# shoe_board.net
KiCad netlist of a schematic drawn in EAGLE
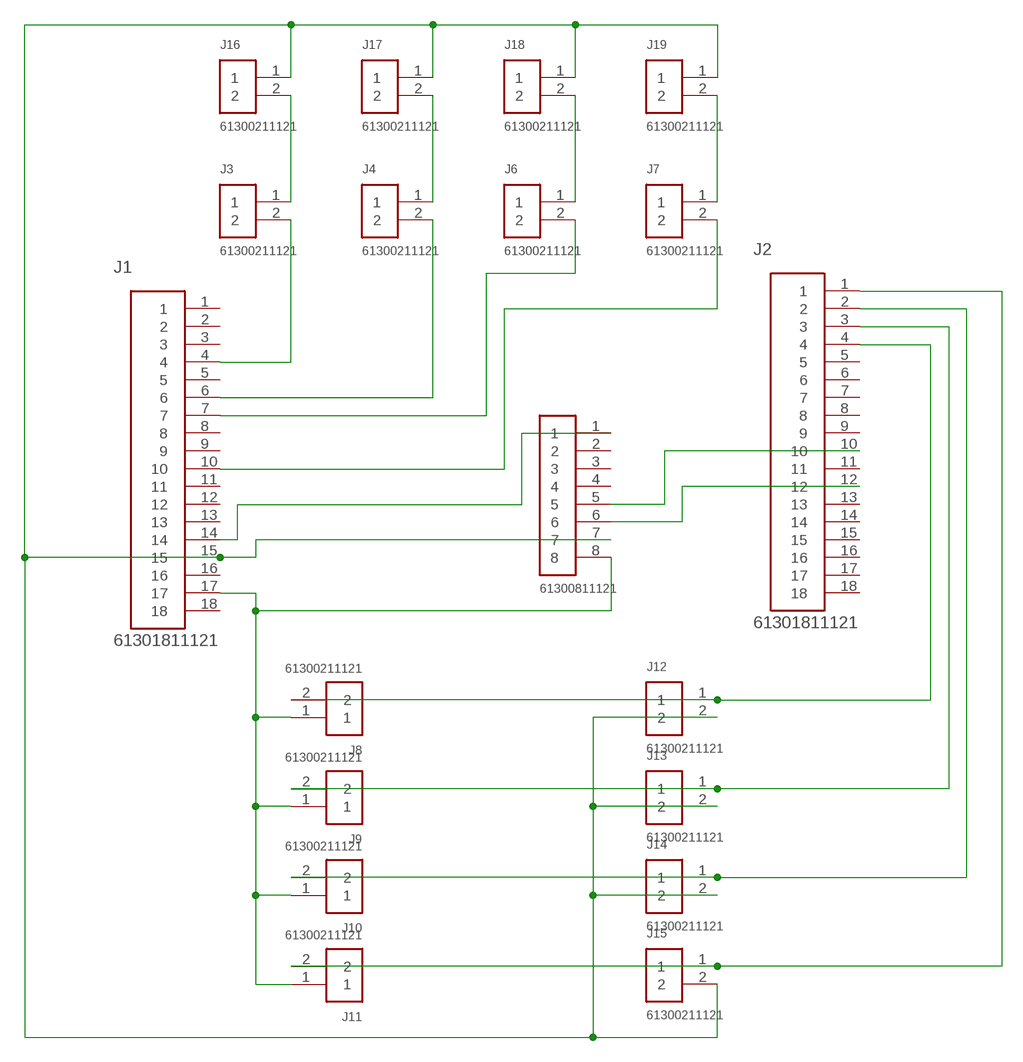
[diagram p0: schematic, sheet 1]

(export (version "E")
  (design (tool "Eeschema 10.0.6"))
  (components
    (comp (ref "J1")
      (value "61301811121")
      (footprint "eagle-import:61301811121")
      (fields
        (field (name "DIGIKEY_PART_NUMBER") "732-5328-ND")
        (field (name "MANUFACTURER") "Wurth Electronics Inc.")
        (field (name "CREATED_BY") "PCBLayout.com")
      )
      (libsource (lib "eagle-import") (part "61301811121"))
    )
    (comp (ref "J2")
      (value "61301811121")
      (footprint "eagle-import:61301811121")
      (fields
        (field (name "DIGIKEY_PART_NUMBER") "732-5328-ND")
        (field (name "MANUFACTURER") "Wurth Electronics Inc.")
        (field (name "CREATED_BY") "PCBLayout.com")
      )
      (libsource (lib "eagle-import") (part "61301811121"))
    )
    (comp (ref "J3")
      (value "61300211121")
      (footprint "eagle-import:61300211121")
      (fields
        (field (name "DIGI_KEY_PART_NUMBER") "732-5315-ND")
        (field (name "MANUFACTURER") "Wurth Electronics Inc.")
        (field (name "CREATED_BY") "PCBLayout.com")
      )
      (libsource (lib "eagle-import") (part "61300211121"))
    )
    (comp (ref "J4")
      (value "61300211121")
      (footprint "eagle-import:61300211121")
      (fields
        (field (name "DIGI_KEY_PART_NUMBER") "732-5315-ND")
        (field (name "MANUFACTURER") "Wurth Electronics Inc.")
        (field (name "CREATED_BY") "PCBLayout.com")
      )
      (libsource (lib "eagle-import") (part "61300211121"))
    )
    (comp (ref "J6")
      (value "61300211121")
      (footprint "eagle-import:61300211121")
      (fields
        (field (name "DIGI_KEY_PART_NUMBER") "732-5315-ND")
        (field (name "MANUFACTURER") "Wurth Electronics Inc.")
        (field (name "CREATED_BY") "PCBLayout.com")
      )
      (libsource (lib "eagle-import") (part "61300211121"))
    )
    (comp (ref "J7")
      (value "61300211121")
      (footprint "eagle-import:61300211121")
      (fields
        (field (name "DIGI_KEY_PART_NUMBER") "732-5315-ND")
        (field (name "MANUFACTURER") "Wurth Electronics Inc.")
        (field (name "CREATED_BY") "PCBLayout.com")
      )
      (libsource (lib "eagle-import") (part "61300211121"))
    )
    (comp (ref "J8")
      (value "61300211121")
      (footprint "eagle-import:61300211121")
      (fields
        (field (name "DIGI_KEY_PART_NUMBER") "732-5315-ND")
        (field (name "MANUFACTURER") "Wurth Electronics Inc.")
        (field (name "CREATED_BY") "PCBLayout.com")
      )
      (libsource (lib "eagle-import") (part "61300211121"))
    )
    (comp (ref "J9")
      (value "61300211121")
      (footprint "eagle-import:61300211121")
      (fields
        (field (name "DIGI_KEY_PART_NUMBER") "732-5315-ND")
        (field (name "MANUFACTURER") "Wurth Electronics Inc.")
        (field (name "CREATED_BY") "PCBLayout.com")
      )
      (libsource (lib "eagle-import") (part "61300211121"))
    )
    (comp (ref "J10")
      (value "61300211121")
      (footprint "eagle-import:61300211121")
      (fields
        (field (name "DIGI_KEY_PART_NUMBER") "732-5315-ND")
        (field (name "MANUFACTURER") "Wurth Electronics Inc.")
        (field (name "CREATED_BY") "PCBLayout.com")
      )
      (libsource (lib "eagle-import") (part "61300211121"))
    )
    (comp (ref "J11")
      (value "61300211121")
      (footprint "eagle-import:61300211121")
      (fields
        (field (name "DIGI_KEY_PART_NUMBER") "732-5315-ND")
        (field (name "MANUFACTURER") "Wurth Electronics Inc.")
        (field (name "CREATED_BY") "PCBLayout.com")
      )
      (libsource (lib "eagle-import") (part "61300211121"))
    )
    (comp (ref "J12")
      (value "61300211121")
      (footprint "eagle-import:61300211121")
      (fields
        (field (name "DIGI_KEY_PART_NUMBER") "732-5315-ND")
        (field (name "MANUFACTURER") "Wurth Electronics Inc.")
        (field (name "CREATED_BY") "PCBLayout.com")
      )
      (libsource (lib "eagle-import") (part "61300211121"))
    )
    (comp (ref "J13")
      (value "61300211121")
      (footprint "eagle-import:61300211121")
      (fields
        (field (name "DIGI_KEY_PART_NUMBER") "732-5315-ND")
        (field (name "MANUFACTURER") "Wurth Electronics Inc.")
        (field (name "CREATED_BY") "PCBLayout.com")
      )
      (libsource (lib "eagle-import") (part "61300211121"))
    )
    (comp (ref "J14")
      (value "61300211121")
      (footprint "eagle-import:61300211121")
      (fields
        (field (name "DIGI_KEY_PART_NUMBER") "732-5315-ND")
        (field (name "MANUFACTURER") "Wurth Electronics Inc.")
        (field (name "CREATED_BY") "PCBLayout.com")
      )
      (libsource (lib "eagle-import") (part "61300211121"))
    )
    (comp (ref "J15")
      (value "61300211121")
      (footprint "eagle-import:61300211121")
      (fields
        (field (name "DIGI_KEY_PART_NUMBER") "732-5315-ND")
        (field (name "MANUFACTURER") "Wurth Electronics Inc.")
        (field (name "CREATED_BY") "PCBLayout.com")
      )
      (libsource (lib "eagle-import") (part "61300211121"))
    )
    (comp (ref "J16")
      (value "61300211121")
      (footprint "eagle-import:61300211121")
      (fields
        (field (name "DIGI_KEY_PART_NUMBER") "732-5315-ND")
        (field (name "MANUFACTURER") "Wurth Electronics Inc.")
        (field (name "CREATED_BY") "PCBLayout.com")
      )
      (libsource (lib "eagle-import") (part "61300211121"))
    )
    (comp (ref "J17")
      (value "61300211121")
      (footprint "eagle-import:61300211121")
      (fields
        (field (name "DIGI_KEY_PART_NUMBER") "732-5315-ND")
        (field (name "MANUFACTURER") "Wurth Electronics Inc.")
        (field (name "CREATED_BY") "PCBLayout.com")
      )
      (libsource (lib "eagle-import") (part "61300211121"))
    )
    (comp (ref "J18")
      (value "61300211121")
      (footprint "eagle-import:61300211121")
      (fields
        (field (name "DIGI_KEY_PART_NUMBER") "732-5315-ND")
        (field (name "MANUFACTURER") "Wurth Electronics Inc.")
        (field (name "CREATED_BY") "PCBLayout.com")
      )
      (libsource (lib "eagle-import") (part "61300211121"))
    )
    (comp (ref "J19")
      (value "61300211121")
      (footprint "eagle-import:61300211121")
      (fields
        (field (name "DIGI_KEY_PART_NUMBER") "732-5315-ND")
        (field (name "MANUFACTURER") "Wurth Electronics Inc.")
        (field (name "CREATED_BY") "PCBLayout.com")
      )
      (libsource (lib "eagle-import") (part "61300211121"))
    )
    (comp (ref "J20")
      (value "61300811121")
      (footprint "eagle-import:61300811121")
      (fields
        (field (name "DIGI_KEY_PART_NUMBER") "732-5321-ND")
        (field (name "MANUFACTURER") "Wurth Electronics Inc.")
        (field (name "CREATED_BY") "PCBLayout.com")
      )
      (libsource (lib "eagle-import") (part "61300811121"))
    )
  )
  (nets
    (net (code "1") (name "Net-(J1-Pad4)") (class "Default")
      (node (ref "J1") (pin "4") (pinfunction "4_4") (pintype "passive"))
      (node (ref "J3") (pin "2") (pinfunction "2_2") (pintype "passive"))
    )
    (net (code "2") (name "Net-(J1-Pad6)") (class "Default")
      (node (ref "J1") (pin "6") (pinfunction "6_6") (pintype "passive"))
      (node (ref "J4") (pin "2") (pinfunction "2_2") (pintype "passive"))
    )
    (net (code "3") (name "Net-(J1-Pad7)") (class "Default")
      (node (ref "J1") (pin "7") (pinfunction "7_7") (pintype "passive"))
      (node (ref "J6") (pin "2") (pinfunction "2_2") (pintype "passive"))
    )
    (net (code "4") (name "Net-(J1-Pad10)") (class "Default")
      (node (ref "J1") (pin "10") (pinfunction "10_10") (pintype "passive"))
      (node (ref "J7") (pin "2") (pinfunction "2_2") (pintype "passive"))
    )
    (net (code "5") (name "Net-(J1-Pad14)") (class "Default")
      (node (ref "J1") (pin "14") (pinfunction "14_14") (pintype "passive"))
      (node (ref "J20") (pin "1") (pinfunction "1_1") (pintype "passive"))
    )
    (net (code "6") (name "Net-(J1-Pad15)") (class "Default")
      (node (ref "J1") (pin "15") (pinfunction "15_15") (pintype "passive"))
      (node (ref "J12") (pin "2") (pinfunction "2_2") (pintype "passive"))
      (node (ref "J13") (pin "2") (pinfunction "2_2") (pintype "passive"))
      (node (ref "J14") (pin "2") (pinfunction "2_2") (pintype "passive"))
      (node (ref "J15") (pin "2") (pinfunction "2_2") (pintype "passive"))
      (node (ref "J16") (pin "1") (pinfunction "1_1") (pintype "passive"))
      (node (ref "J17") (pin "1") (pinfunction "1_1") (pintype "passive"))
      (node (ref "J18") (pin "1") (pinfunction "1_1") (pintype "passive"))
      (node (ref "J19") (pin "1") (pinfunction "1_1") (pintype "passive"))
      (node (ref "J20") (pin "7") (pinfunction "7_7") (pintype "passive"))
    )
    (net (code "7") (name "Net-(J1-Pad17)") (class "Default")
      (node (ref "J1") (pin "17") (pinfunction "17_17") (pintype "passive"))
      (node (ref "J10") (pin "1") (pinfunction "1_1") (pintype "passive"))
      (node (ref "J11") (pin "1") (pinfunction "1_1") (pintype "passive"))
      (node (ref "J20") (pin "8") (pinfunction "8_8") (pintype "passive"))
      (node (ref "J8") (pin "1") (pinfunction "1_1") (pintype "passive"))
      (node (ref "J9") (pin "1") (pinfunction "1_1") (pintype "passive"))
    )
    (net (code "8") (name "Net-(J2-Pad10)") (class "Default")
      (node (ref "J2") (pin "10") (pinfunction "10_10") (pintype "passive"))
      (node (ref "J20") (pin "5") (pinfunction "5_5") (pintype "passive"))
    )
    (net (code "9") (name "Net-(J2-Pad12)") (class "Default")
      (node (ref "J2") (pin "12") (pinfunction "12_12") (pintype "passive"))
      (node (ref "J20") (pin "6") (pinfunction "6_6") (pintype "passive"))
    )
    (net (code "10") (name "Net-(J10-Pad2)") (class "Default")
      (node (ref "J10") (pin "2") (pinfunction "2_2") (pintype "passive"))
      (node (ref "J14") (pin "1") (pinfunction "1_1") (pintype "passive"))
      (node (ref "J2") (pin "2") (pinfunction "2_2") (pintype "passive"))
    )
    (net (code "11") (name "Net-(J11-Pad2)") (class "Default")
      (node (ref "J11") (pin "2") (pinfunction "2_2") (pintype "passive"))
      (node (ref "J15") (pin "1") (pinfunction "1_1") (pintype "passive"))
      (node (ref "J2") (pin "1") (pinfunction "1_1") (pintype "passive"))
    )
    (net (code "12") (name "Net-(J12-Pad1)") (class "Default")
      (node (ref "J12") (pin "1") (pinfunction "1_1") (pintype "passive"))
      (node (ref "J2") (pin "4") (pinfunction "4_4") (pintype "passive"))
      (node (ref "J8") (pin "2") (pinfunction "2_2") (pintype "passive"))
    )
    (net (code "13") (name "Net-(J13-Pad1)") (class "Default")
      (node (ref "J13") (pin "1") (pinfunction "1_1") (pintype "passive"))
      (node (ref "J2") (pin "3") (pinfunction "3_3") (pintype "passive"))
      (node (ref "J9") (pin "2") (pinfunction "2_2") (pintype "passive"))
    )
    (net (code "14") (name "Net-(J16-Pad2)") (class "Default")
      (node (ref "J16") (pin "2") (pinfunction "2_2") (pintype "passive"))
      (node (ref "J3") (pin "1") (pinfunction "1_1") (pintype "passive"))
    )
    (net (code "15") (name "Net-(J17-Pad2)") (class "Default")
      (node (ref "J17") (pin "2") (pinfunction "2_2") (pintype "passive"))
      (node (ref "J4") (pin "1") (pinfunction "1_1") (pintype "passive"))
    )
    (net (code "16") (name "Net-(J18-Pad2)") (class "Default")
      (node (ref "J18") (pin "2") (pinfunction "2_2") (pintype "passive"))
      (node (ref "J6") (pin "1") (pinfunction "1_1") (pintype "passive"))
    )
    (net (code "17") (name "Net-(J19-Pad2)") (class "Default")
      (node (ref "J19") (pin "2") (pinfunction "2_2") (pintype "passive"))
      (node (ref "J7") (pin "1") (pinfunction "1_1") (pintype "passive"))
    )
    (net (code "18") (name "unconnected-(J1-Pad1)") (class "Default")
      (node (ref "J1") (pin "1") (pinfunction "1_1") (pintype "passive"))
    )
    (net (code "19") (name "unconnected-(J1-Pad2)") (class "Default")
      (node (ref "J1") (pin "2") (pinfunction "2_2") (pintype "passive"))
    )
    (net (code "20") (name "unconnected-(J1-Pad3)") (class "Default")
      (node (ref "J1") (pin "3") (pinfunction "3_3") (pintype "passive"))
    )
    (net (code "21") (name "unconnected-(J1-Pad5)") (class "Default")
      (node (ref "J1") (pin "5") (pinfunction "5_5") (pintype "passive"))
    )
    (net (code "22") (name "unconnected-(J1-Pad8)") (class "Default")
      (node (ref "J1") (pin "8") (pinfunction "8_8") (pintype "passive"))
    )
    (net (code "23") (name "unconnected-(J1-Pad9)") (class "Default")
      (node (ref "J1") (pin "9") (pinfunction "9_9") (pintype "passive"))
    )
    (net (code "24") (name "unconnected-(J1-Pad11)") (class "Default")
      (node (ref "J1") (pin "11") (pinfunction "11_11") (pintype "passive"))
    )
    (net (code "25") (name "unconnected-(J1-Pad12)") (class "Default")
      (node (ref "J1") (pin "12") (pinfunction "12_12") (pintype "passive"))
    )
    (net (code "26") (name "unconnected-(J1-Pad13)") (class "Default")
      (node (ref "J1") (pin "13") (pinfunction "13_13") (pintype "passive"))
    )
    (net (code "27") (name "unconnected-(J1-Pad16)") (class "Default")
      (node (ref "J1") (pin "16") (pinfunction "16_16") (pintype "passive"))
    )
    (net (code "28") (name "unconnected-(J1-Pad18)") (class "Default")
      (node (ref "J1") (pin "18") (pinfunction "18_18") (pintype "passive"))
    )
    (net (code "29") (name "unconnected-(J2-Pad5)") (class "Default")
      (node (ref "J2") (pin "5") (pinfunction "5_5") (pintype "passive"))
    )
    (net (code "30") (name "unconnected-(J2-Pad6)") (class "Default")
      (node (ref "J2") (pin "6") (pinfunction "6_6") (pintype "passive"))
    )
    (net (code "31") (name "unconnected-(J2-Pad7)") (class "Default")
      (node (ref "J2") (pin "7") (pinfunction "7_7") (pintype "passive"))
    )
    (net (code "32") (name "unconnected-(J2-Pad8)") (class "Default")
      (node (ref "J2") (pin "8") (pinfunction "8_8") (pintype "passive"))
    )
    (net (code "33") (name "unconnected-(J2-Pad9)") (class "Default")
      (node (ref "J2") (pin "9") (pinfunction "9_9") (pintype "passive"))
    )
    (net (code "34") (name "unconnected-(J2-Pad11)") (class "Default")
      (node (ref "J2") (pin "11") (pinfunction "11_11") (pintype "passive"))
    )
    (net (code "35") (name "unconnected-(J2-Pad13)") (class "Default")
      (node (ref "J2") (pin "13") (pinfunction "13_13") (pintype "passive"))
    )
    (net (code "36") (name "unconnected-(J2-Pad14)") (class "Default")
      (node (ref "J2") (pin "14") (pinfunction "14_14") (pintype "passive"))
    )
    (net (code "37") (name "unconnected-(J2-Pad15)") (class "Default")
      (node (ref "J2") (pin "15") (pinfunction "15_15") (pintype "passive"))
    )
    (net (code "38") (name "unconnected-(J2-Pad16)") (class "Default")
      (node (ref "J2") (pin "16") (pinfunction "16_16") (pintype "passive"))
    )
    (net (code "39") (name "unconnected-(J2-Pad17)") (class "Default")
      (node (ref "J2") (pin "17") (pinfunction "17_17") (pintype "passive"))
    )
    (net (code "40") (name "unconnected-(J2-Pad18)") (class "Default")
      (node (ref "J2") (pin "18") (pinfunction "18_18") (pintype "passive"))
    )
    (net (code "41") (name "unconnected-(J20-Pad2)") (class "Default")
      (node (ref "J20") (pin "2") (pinfunction "2_2") (pintype "passive"))
    )
    (net (code "42") (name "unconnected-(J20-Pad3)") (class "Default")
      (node (ref "J20") (pin "3") (pinfunction "3_3") (pintype "passive"))
    )
    (net (code "43") (name "unconnected-(J20-Pad4)") (class "Default")
      (node (ref "J20") (pin "4") (pinfunction "4_4") (pintype "passive"))
    )
  )
)
